# grove_shield_v02.net
KiCad netlist of a schematic drawn in EAGLE
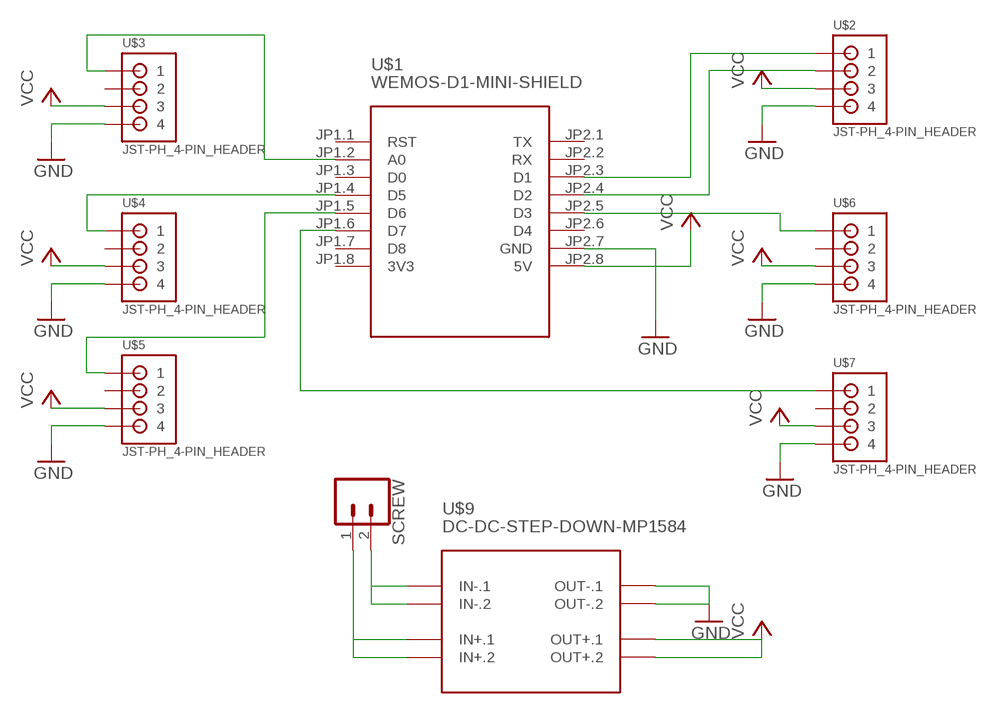
[diagram p0: schematic, sheet 1]

(export (version "E")
  (design (tool "Eeschema 10.0.6"))
  (components
    (comp (ref "SCREW")
      (value "CONN_025MM")
      (footprint "eagle-import:SCREWTERMINAL-5MM-2")
      (libsource (lib "eagle-import") (part "CONN_025MM"))
    )
    (comp (ref "U$1")
      (value "WEMOS-D1-MINI-SHIELD")
      (footprint "eagle-import:WEMOS-D1-MINI-SHIELD")
      (libsource (lib "eagle-import") (part "WEMOS-D1-MINI-SHIELD"))
    )
    (comp (ref "U$2")
      (value "JST-PH_4-PIN_HEADER")
      (footprint "eagle-import:JST_B4B-PH_HEADER")
      (libsource (lib "eagle-import") (part "JST-PH_4-PIN_HEADER"))
    )
    (comp (ref "U$3")
      (value "JST-PH_4-PIN_HEADER")
      (footprint "eagle-import:JST_B4B-PH_HEADER")
      (libsource (lib "eagle-import") (part "JST-PH_4-PIN_HEADER"))
    )
    (comp (ref "U$4")
      (value "JST-PH_4-PIN_HEADER")
      (footprint "eagle-import:JST_B4B-PH_HEADER")
      (libsource (lib "eagle-import") (part "JST-PH_4-PIN_HEADER"))
    )
    (comp (ref "U$5")
      (value "JST-PH_4-PIN_HEADER")
      (footprint "eagle-import:JST_B4B-PH_HEADER")
      (libsource (lib "eagle-import") (part "JST-PH_4-PIN_HEADER"))
    )
    (comp (ref "U$6")
      (value "JST-PH_4-PIN_HEADER")
      (footprint "eagle-import:JST_B4B-PH_HEADER")
      (libsource (lib "eagle-import") (part "JST-PH_4-PIN_HEADER"))
    )
    (comp (ref "U$7")
      (value "JST-PH_4-PIN_HEADER")
      (footprint "eagle-import:JST_B4B-PH_HEADER")
      (libsource (lib "eagle-import") (part "JST-PH_4-PIN_HEADER"))
    )
    (comp (ref "U$9")
      (value "DC-DC-STEP-DOWN-MP1584")
      (footprint "eagle-import:DC-DC-STEP-DOWN-MP1584")
      (libsource (lib "eagle-import") (part "DC-DC-STEP-DOWN-MP1584"))
    )
  )
  (nets
    (net (code "1") (name "/3V3") (class "Default")
      (node (ref "U$1") (pin "JP1.8") (pinfunction "3V3_JP1.8") (pintype "power_in"))
    )
    (net (code "2") (name "GND") (class "Default")
      (node (ref "U$1") (pin "JP2.7") (pinfunction "GND_JP2.7") (pintype "power_in"))
      (node (ref "U$2") (pin "P4") (pinfunction "4_P4") (pintype "bidirectional"))
      (node (ref "U$3") (pin "P4") (pinfunction "4_P4") (pintype "bidirectional"))
      (node (ref "U$4") (pin "P4") (pinfunction "4_P4") (pintype "bidirectional"))
      (node (ref "U$5") (pin "P4") (pinfunction "4_P4") (pintype "bidirectional"))
      (node (ref "U$6") (pin "P4") (pinfunction "4_P4") (pintype "bidirectional"))
      (node (ref "U$7") (pin "P4") (pinfunction "4_P4") (pintype "bidirectional"))
      (node (ref "U$9") (pin "OUT-.1") (pinfunction "OUT-.1_OUT-.1") (pintype "bidirectional"))
      (node (ref "U$9") (pin "OUT-.2") (pinfunction "OUT-.2_OUT-.2") (pintype "bidirectional"))
    )
    (net (code "3") (name "Net-(SCREW-Pad1)") (class "Default")
      (node (ref "SCREW") (pin "1") (pinfunction "1_1") (pintype "passive"))
      (node (ref "U$9") (pin "IN+.1") (pinfunction "IN+.1_IN+.1") (pintype "bidirectional"))
      (node (ref "U$9") (pin "IN+.2") (pinfunction "IN+.2_IN+.2") (pintype "bidirectional"))
    )
    (net (code "4") (name "Net-(SCREW-Pad2)") (class "Default")
      (node (ref "SCREW") (pin "2") (pinfunction "2_2") (pintype "passive"))
      (node (ref "U$9") (pin "IN-.1") (pinfunction "IN-.1_IN-.1") (pintype "bidirectional"))
      (node (ref "U$9") (pin "IN-.2") (pinfunction "IN-.2_IN-.2") (pintype "bidirectional"))
    )
    (net (code "5") (name "Net-(U$1-A0)") (class "Default")
      (node (ref "U$1") (pin "JP1.2") (pinfunction "A0_JP1.2") (pintype "bidirectional"))
      (node (ref "U$3") (pin "P1") (pinfunction "1_P1") (pintype "bidirectional"))
    )
    (net (code "6") (name "Net-(U$1-D1)") (class "Default")
      (node (ref "U$1") (pin "JP2.3") (pinfunction "D1_JP2.3") (pintype "bidirectional"))
      (node (ref "U$2") (pin "P1") (pinfunction "1_P1") (pintype "bidirectional"))
    )
    (net (code "7") (name "Net-(U$1-D2)") (class "Default")
      (node (ref "U$1") (pin "JP2.4") (pinfunction "D2_JP2.4") (pintype "bidirectional"))
      (node (ref "U$2") (pin "P2") (pinfunction "2_P2") (pintype "bidirectional"))
    )
    (net (code "8") (name "Net-(U$1-D3)") (class "Default")
      (node (ref "U$1") (pin "JP2.5") (pinfunction "D3_JP2.5") (pintype "bidirectional"))
      (node (ref "U$6") (pin "P1") (pinfunction "1_P1") (pintype "bidirectional"))
    )
    (net (code "9") (name "Net-(U$1-D5)") (class "Default")
      (node (ref "U$1") (pin "JP1.4") (pinfunction "D5_JP1.4") (pintype "bidirectional"))
      (node (ref "U$4") (pin "P1") (pinfunction "1_P1") (pintype "bidirectional"))
    )
    (net (code "10") (name "Net-(U$1-D6)") (class "Default")
      (node (ref "U$1") (pin "JP1.5") (pinfunction "D6_JP1.5") (pintype "bidirectional"))
      (node (ref "U$5") (pin "P1") (pinfunction "1_P1") (pintype "bidirectional"))
    )
    (net (code "11") (name "Net-(U$1-D7)") (class "Default")
      (node (ref "U$1") (pin "JP1.6") (pinfunction "D7_JP1.6") (pintype "bidirectional"))
      (node (ref "U$7") (pin "P1") (pinfunction "1_P1") (pintype "bidirectional"))
    )
    (net (code "12") (name "VCC") (class "Default")
      (node (ref "U$1") (pin "JP2.8") (pinfunction "5V_JP2.8") (pintype "power_in"))
      (node (ref "U$2") (pin "P3") (pinfunction "3_P3") (pintype "bidirectional"))
      (node (ref "U$3") (pin "P3") (pinfunction "3_P3") (pintype "bidirectional"))
      (node (ref "U$4") (pin "P3") (pinfunction "3_P3") (pintype "bidirectional"))
      (node (ref "U$5") (pin "P3") (pinfunction "3_P3") (pintype "bidirectional"))
      (node (ref "U$6") (pin "P3") (pinfunction "3_P3") (pintype "bidirectional"))
      (node (ref "U$7") (pin "P3") (pinfunction "3_P3") (pintype "bidirectional"))
      (node (ref "U$9") (pin "OUT+.1") (pinfunction "OUT+.1_OUT+.1") (pintype "bidirectional"))
      (node (ref "U$9") (pin "OUT+.2") (pinfunction "OUT+.2_OUT+.2") (pintype "bidirectional"))
    )
    (net (code "13") (name "unconnected-(U$1-D0-PadJP1.3)") (class "Default")
      (node (ref "U$1") (pin "JP1.3") (pinfunction "D0_JP1.3") (pintype "bidirectional"))
    )
    (net (code "14") (name "unconnected-(U$1-D4-PadJP2.6)") (class "Default")
      (node (ref "U$1") (pin "JP2.6") (pinfunction "D4_JP2.6") (pintype "bidirectional"))
    )
    (net (code "15") (name "unconnected-(U$1-D8-PadJP1.7)") (class "Default")
      (node (ref "U$1") (pin "JP1.7") (pinfunction "D8_JP1.7") (pintype "bidirectional"))
    )
    (net (code "16") (name "unconnected-(U$1-RST-PadJP1.1)") (class "Default")
      (node (ref "U$1") (pin "JP1.1") (pinfunction "RST_JP1.1") (pintype "bidirectional"))
    )
    (net (code "17") (name "unconnected-(U$1-RX-PadJP2.2)") (class "Default")
      (node (ref "U$1") (pin "JP2.2") (pinfunction "RX_JP2.2") (pintype "bidirectional"))
    )
    (net (code "18") (name "unconnected-(U$1-TX-PadJP2.1)") (class "Default")
      (node (ref "U$1") (pin "JP2.1") (pinfunction "TX_JP2.1") (pintype "bidirectional"))
    )
    (net (code "19") (name "unconnected-(U$3-2-PadP2)") (class "Default")
      (node (ref "U$3") (pin "P2") (pinfunction "2_P2") (pintype "bidirectional"))
    )
    (net (code "20") (name "unconnected-(U$4-2-PadP2)") (class "Default")
      (node (ref "U$4") (pin "P2") (pinfunction "2_P2") (pintype "bidirectional"))
    )
    (net (code "21") (name "unconnected-(U$5-2-PadP2)") (class "Default")
      (node (ref "U$5") (pin "P2") (pinfunction "2_P2") (pintype "bidirectional"))
    )
    (net (code "22") (name "unconnected-(U$6-2-PadP2)") (class "Default")
      (node (ref "U$6") (pin "P2") (pinfunction "2_P2") (pintype "bidirectional"))
    )
    (net (code "23") (name "unconnected-(U$7-2-PadP2)") (class "Default")
      (node (ref "U$7") (pin "P2") (pinfunction "2_P2") (pintype "bidirectional"))
    )
  )
)
